# board_wifi_v2.net
KiCad netlist of a schematic drawn in EAGLE
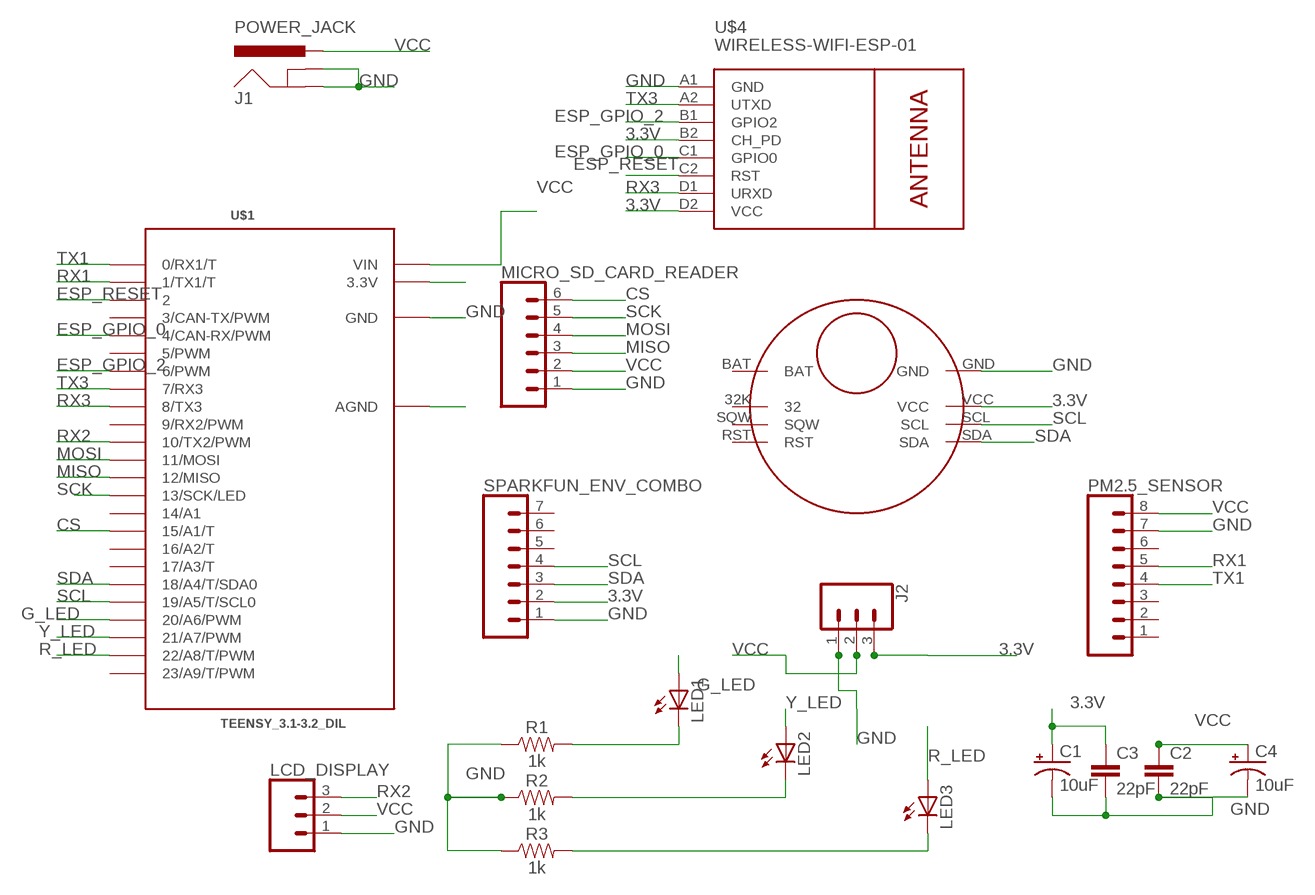
[diagram p0: schematic, sheet 1]

(export (version "E")
  (design (tool "Eeschema 10.0.6"))
  (components
    (comp (ref "C1")
      (value "10uF")
      (footprint "eagle-import:CPOL-RADIAL-2.5MM-5MM")
      (libsource (lib "eagle-import") (part "10UF-POLAR-RADIAL-2.5MM-25V-20%"))
    )
    (comp (ref "C2")
      (value "22pF")
      (footprint "eagle-import:CAP-PTH-2.54")
      (libsource (lib "eagle-import") (part "22PF-PTH-2.54MM-200V-5%"))
    )
    (comp (ref "C3")
      (value "22pF")
      (footprint "eagle-import:CAP-PTH-2.54")
      (libsource (lib "eagle-import") (part "22PF-PTH-2.54MM-200V-5%"))
    )
    (comp (ref "C4")
      (value "10uF")
      (footprint "eagle-import:CPOL-RADIAL-2.5MM-5MM")
      (libsource (lib "eagle-import") (part "10UF-POLAR-RADIAL-2.5MM-25V-20%"))
    )
    (comp (ref "J1")
      (value "POWER_JACK")
      (footprint "eagle-import:POWER_JACK_PTH")
      (libsource (lib "eagle-import") (part "POWER_JACK"))
    )
    (comp (ref "J2")
      (value "CONN_03LONGPADS")
      (footprint "eagle-import:1X03_LONGPADS")
      (libsource (lib "eagle-import") (part "CONN_03LONGPADS"))
    )
    (comp (ref "LCD_DISPLAY")
      (value "CONN_031X03_NO_SILK")
      (footprint "eagle-import:1X03_NO_SILK")
      (libsource (lib "eagle-import") (part "CONN_031X03_NO_SILK"))
    )
    (comp (ref "LED1")
      (value "LED3MM")
      (footprint "eagle-import:LED3MM")
      (libsource (lib "eagle-import") (part "LED3MM"))
    )
    (comp (ref "LED2")
      (value "LED3MM")
      (footprint "eagle-import:LED3MM")
      (libsource (lib "eagle-import") (part "LED3MM"))
    )
    (comp (ref "LED3")
      (value "LED3MM")
      (footprint "eagle-import:LED3MM")
      (libsource (lib "eagle-import") (part "LED3MM"))
    )
    (comp (ref "MICRO_SD_CARD_READER")
      (value "CONN_06LONGPADS")
      (footprint "eagle-import:1X06_LONGPADS")
      (libsource (lib "eagle-import") (part "CONN_06LONGPADS"))
    )
    (comp (ref "PM2.5_SENSOR")
      (value "CONN_08NO_SILK_FEMALE_PTH")
      (footprint "eagle-import:1X08_NO_SILK")
      (libsource (lib "eagle-import") (part "CONN_08NO_SILK_FEMALE_PTH"))
    )
    (comp (ref "R1")
      (value "1k")
      (footprint "eagle-import:AXIAL-0.3")
      (libsource (lib "eagle-import") (part "1KOHM-HORIZ-1/4W-5%"))
    )
    (comp (ref "R2")
      (value "1k")
      (footprint "eagle-import:AXIAL-0.3")
      (libsource (lib "eagle-import") (part "1KOHM-HORIZ-1/4W-5%"))
    )
    (comp (ref "R3")
      (value "1k")
      (footprint "eagle-import:AXIAL-0.3")
      (libsource (lib "eagle-import") (part "1KOHM-HORIZ-1/4W-5%"))
    )
    (comp (ref "SPARKFUN_ENV_COMBO")
      (value "CONN_07NO_SILK")
      (footprint "eagle-import:1X07_NO_SILK")
      (libsource (lib "eagle-import") (part "CONN_07NO_SILK"))
    )
    (comp (ref "U$1")
      (value "TEENSY_3.1-3.2_DIL")
      (footprint "eagle-import:TEENSY_3.0-3.2&LC_DIL")
      (libsource (lib "eagle-import") (part "TEENSY_3.1-3.2_DIL"))
    )
    (comp (ref "U$2")
      (value "RTCCLOCK")
      (footprint "eagle-import:RTCCLOCK")
      (libsource (lib "eagle-import") (part "RTCCLOCK"))
    )
    (comp (ref "U$4")
      (value "WIRELESS-WIFI-ESP-01")
      (footprint "eagle-import:WIRELESS-WIFI-ESP-01")
      (libsource (lib "eagle-import") (part "WIRELESS-WIFI-ESP-01"))
    )
  )
  (nets
    (net (code "1") (name "/3.3V") (class "Default")
      (node (ref "C1") (pin "1") (pinfunction "+_1") (pintype "passive"))
      (node (ref "C3") (pin "1") (pinfunction "1_1") (pintype "passive"))
      (node (ref "J2") (pin "3") (pinfunction "3_3") (pintype "passive"))
      (node (ref "SPARKFUN_ENV_COMBO") (pin "2") (pinfunction "2_2") (pintype "passive"))
      (node (ref "U$2") (pin "VCC") (pinfunction "VCC_VCC") (pintype "bidirectional"))
      (node (ref "U$4") (pin "B2") (pinfunction "CH_PD_B2") (pintype "bidirectional"))
      (node (ref "U$4") (pin "D2") (pinfunction "VCC_D2") (pintype "power_in"))
    )
    (net (code "2") (name "/CS") (class "Default")
      (node (ref "MICRO_SD_CARD_READER") (pin "6") (pinfunction "6_6") (pintype "passive"))
      (node (ref "U$1") (pin "15/A1") (pinfunction "15/A1/T_15/A1") (pintype "bidirectional"))
    )
    (net (code "3") (name "/ESP_GPIO_0") (class "Default")
      (node (ref "U$1") (pin "4") (pinfunction "4/CAN-RX/PWM_4") (pintype "bidirectional"))
      (node (ref "U$4") (pin "C1") (pinfunction "GPIO0_C1") (pintype "bidirectional"))
    )
    (net (code "4") (name "/ESP_GPIO_2") (class "Default")
      (node (ref "U$1") (pin "6") (pinfunction "6/PWM_6") (pintype "bidirectional"))
      (node (ref "U$4") (pin "B1") (pinfunction "GPIO2_B1") (pintype "bidirectional"))
    )
    (net (code "5") (name "/ESP_RESET") (class "Default")
      (node (ref "U$1") (pin "2") (pinfunction "2_2") (pintype "bidirectional"))
      (node (ref "U$4") (pin "C2") (pinfunction "RST_C2") (pintype "bidirectional"))
    )
    (net (code "6") (name "/GND") (class "Default")
      (node (ref "C1") (pin "2") (pinfunction "-_2") (pintype "passive"))
      (node (ref "C2") (pin "2") (pinfunction "2_2") (pintype "passive"))
      (node (ref "C3") (pin "2") (pinfunction "2_2") (pintype "passive"))
      (node (ref "C4") (pin "2") (pinfunction "-_2") (pintype "passive"))
      (node (ref "J1") (pin "GND") (pinfunction "GND_GND") (pintype "bidirectional"))
      (node (ref "J1") (pin "GNDBREAK") (pinfunction "GNDBREAK_GNDBREAK") (pintype "bidirectional"))
      (node (ref "J2") (pin "1") (pinfunction "1_1") (pintype "passive"))
      (node (ref "LCD_DISPLAY") (pin "1") (pinfunction "1_1") (pintype "passive"))
      (node (ref "MICRO_SD_CARD_READER") (pin "1") (pinfunction "1_1") (pintype "passive"))
      (node (ref "PM2.5_SENSOR") (pin "7") (pinfunction "7_7") (pintype "passive"))
      (node (ref "R1") (pin "P$1") (pinfunction "1_P$1") (pintype "passive"))
      (node (ref "R2") (pin "P$1") (pinfunction "1_P$1") (pintype "passive"))
      (node (ref "R3") (pin "P$1") (pinfunction "1_P$1") (pintype "passive"))
      (node (ref "SPARKFUN_ENV_COMBO") (pin "1") (pinfunction "1_1") (pintype "passive"))
      (node (ref "U$1") (pin "GND") (pinfunction "GND_GND") (pintype "power_in"))
      (node (ref "U$2") (pin "GND") (pinfunction "GND_GND") (pintype "bidirectional"))
      (node (ref "U$4") (pin "A1") (pinfunction "GND_A1") (pintype "power_in"))
    )
    (net (code "7") (name "/G_LED") (class "Default")
      (node (ref "LED1") (pin "A") (pinfunction "A_A") (pintype "passive"))
      (node (ref "U$1") (pin "20/A6") (pinfunction "20/A6/PWM_20/A6") (pintype "bidirectional"))
    )
    (net (code "8") (name "/MISO") (class "Default")
      (node (ref "MICRO_SD_CARD_READER") (pin "3") (pinfunction "3_3") (pintype "passive"))
      (node (ref "U$1") (pin "12") (pinfunction "12/MISO_12") (pintype "bidirectional"))
    )
    (net (code "9") (name "/MOSI") (class "Default")
      (node (ref "MICRO_SD_CARD_READER") (pin "4") (pinfunction "4_4") (pintype "passive"))
      (node (ref "U$1") (pin "11") (pinfunction "11/MOSI_11") (pintype "bidirectional"))
    )
    (net (code "10") (name "/RX1") (class "Default")
      (node (ref "PM2.5_SENSOR") (pin "5") (pinfunction "5_5") (pintype "passive"))
      (node (ref "U$1") (pin "1") (pinfunction "1/TX1/T_1") (pintype "bidirectional"))
    )
    (net (code "11") (name "/RX2") (class "Default")
      (node (ref "LCD_DISPLAY") (pin "3") (pinfunction "3_3") (pintype "passive"))
      (node (ref "U$1") (pin "10") (pinfunction "10/TX2/PWM_10") (pintype "bidirectional"))
    )
    (net (code "12") (name "/RX3") (class "Default")
      (node (ref "U$1") (pin "8") (pinfunction "8/TX3_8") (pintype "bidirectional"))
      (node (ref "U$4") (pin "D1") (pinfunction "URXD_D1") (pintype "bidirectional"))
    )
    (net (code "13") (name "/R_LED") (class "Default")
      (node (ref "LED3") (pin "A") (pinfunction "A_A") (pintype "passive"))
      (node (ref "U$1") (pin "22/A8") (pinfunction "22/A8/T/PWM_22/A8") (pintype "bidirectional"))
    )
    (net (code "14") (name "/SCK") (class "Default")
      (node (ref "MICRO_SD_CARD_READER") (pin "5") (pinfunction "5_5") (pintype "passive"))
      (node (ref "U$1") (pin "13") (pinfunction "13/SCK/LED_13") (pintype "bidirectional"))
    )
    (net (code "15") (name "/SCL") (class "Default")
      (node (ref "SPARKFUN_ENV_COMBO") (pin "4") (pinfunction "4_4") (pintype "passive"))
      (node (ref "U$1") (pin "19/A5") (pinfunction "19/A5/T/SCL0_19/A5") (pintype "bidirectional"))
      (node (ref "U$2") (pin "SCL") (pinfunction "SCL_SCL") (pintype "bidirectional"))
    )
    (net (code "16") (name "/SDA") (class "Default")
      (node (ref "SPARKFUN_ENV_COMBO") (pin "3") (pinfunction "3_3") (pintype "passive"))
      (node (ref "U$1") (pin "18/A4") (pinfunction "18/A4/T/SDA0_18/A4") (pintype "bidirectional"))
      (node (ref "U$2") (pin "SDA") (pinfunction "SDA_SDA") (pintype "bidirectional"))
    )
    (net (code "17") (name "/TX1") (class "Default")
      (node (ref "PM2.5_SENSOR") (pin "4") (pinfunction "4_4") (pintype "passive"))
      (node (ref "U$1") (pin "0") (pinfunction "0/RX1/T_0") (pintype "bidirectional"))
    )
    (net (code "18") (name "/TX3") (class "Default")
      (node (ref "U$1") (pin "7") (pinfunction "7/RX3_7") (pintype "bidirectional"))
      (node (ref "U$4") (pin "A2") (pinfunction "UTXD_A2") (pintype "bidirectional"))
    )
    (net (code "19") (name "/VCC") (class "Default")
      (node (ref "C2") (pin "1") (pinfunction "1_1") (pintype "passive"))
      (node (ref "C4") (pin "1") (pinfunction "+_1") (pintype "passive"))
      (node (ref "J1") (pin "PWR") (pinfunction "PWR_PWR") (pintype "bidirectional"))
      (node (ref "J2") (pin "2") (pinfunction "2_2") (pintype "passive"))
      (node (ref "LCD_DISPLAY") (pin "2") (pinfunction "2_2") (pintype "passive"))
      (node (ref "MICRO_SD_CARD_READER") (pin "2") (pinfunction "2_2") (pintype "passive"))
      (node (ref "PM2.5_SENSOR") (pin "8") (pinfunction "8_8") (pintype "passive"))
      (node (ref "U$1") (pin "VIN") (pinfunction "VIN_VIN") (pintype "power_in"))
    )
    (net (code "20") (name "/Y_LED") (class "Default")
      (node (ref "LED2") (pin "A") (pinfunction "A_A") (pintype "passive"))
      (node (ref "U$1") (pin "21/A7") (pinfunction "21/A7/PWM_21/A7") (pintype "bidirectional"))
    )
    (net (code "21") (name "Net-(LED1-C)") (class "Default")
      (node (ref "LED1") (pin "K") (pinfunction "C_K") (pintype "passive"))
      (node (ref "R1") (pin "P$2") (pinfunction "2_P$2") (pintype "passive"))
    )
    (net (code "22") (name "Net-(LED2-C)") (class "Default")
      (node (ref "LED2") (pin "K") (pinfunction "C_K") (pintype "passive"))
      (node (ref "R2") (pin "P$2") (pinfunction "2_P$2") (pintype "passive"))
    )
    (net (code "23") (name "Net-(LED3-C)") (class "Default")
      (node (ref "LED3") (pin "K") (pinfunction "C_K") (pintype "passive"))
      (node (ref "R3") (pin "P$2") (pinfunction "2_P$2") (pintype "passive"))
    )
    (net (code "24") (name "unconnected-(PM2.5_SENSOR-Pad1)") (class "Default")
      (node (ref "PM2.5_SENSOR") (pin "1") (pinfunction "1_1") (pintype "passive"))
    )
    (net (code "25") (name "unconnected-(PM2.5_SENSOR-Pad2)") (class "Default")
      (node (ref "PM2.5_SENSOR") (pin "2") (pinfunction "2_2") (pintype "passive"))
    )
    (net (code "26") (name "unconnected-(PM2.5_SENSOR-Pad3)") (class "Default")
      (node (ref "PM2.5_SENSOR") (pin "3") (pinfunction "3_3") (pintype "passive"))
    )
    (net (code "27") (name "unconnected-(PM2.5_SENSOR-Pad6)") (class "Default")
      (node (ref "PM2.5_SENSOR") (pin "6") (pinfunction "6_6") (pintype "passive"))
    )
    (net (code "28") (name "unconnected-(SPARKFUN_ENV_COMBO-Pad5)") (class "Default")
      (node (ref "SPARKFUN_ENV_COMBO") (pin "5") (pinfunction "5_5") (pintype "passive"))
    )
    (net (code "29") (name "unconnected-(SPARKFUN_ENV_COMBO-Pad6)") (class "Default")
      (node (ref "SPARKFUN_ENV_COMBO") (pin "6") (pinfunction "6_6") (pintype "passive"))
    )
    (net (code "30") (name "unconnected-(SPARKFUN_ENV_COMBO-Pad7)") (class "Default")
      (node (ref "SPARKFUN_ENV_COMBO") (pin "7") (pinfunction "7_7") (pintype "passive"))
    )
    (net (code "31") (name "unconnected-(U$1-3{slash}CAN-TX{slash}PWM-Pad3)") (class "Default")
      (node (ref "U$1") (pin "3") (pinfunction "3/CAN-TX/PWM_3") (pintype "bidirectional"))
    )
    (net (code "32") (name "unconnected-(U$1-5{slash}PWM-Pad5)") (class "Default")
      (node (ref "U$1") (pin "5") (pinfunction "5/PWM_5") (pintype "bidirectional"))
    )
    (net (code "33") (name "unconnected-(U$1-9{slash}RX2{slash}PWM-Pad9)") (class "Default")
      (node (ref "U$1") (pin "9") (pinfunction "9/RX2/PWM_9") (pintype "bidirectional"))
    )
    (net (code "34") (name "unconnected-(U$1-14{slash}A1-Pad14{slash}A0)") (class "Default")
      (node (ref "U$1") (pin "14/A0") (pinfunction "14/A1_14/A0") (pintype "bidirectional"))
    )
    (net (code "35") (name "unconnected-(U$1-16{slash}A2{slash}T-Pad16{slash}A2)") (class "Default")
      (node (ref "U$1") (pin "16/A2") (pinfunction "16/A2/T_16/A2") (pintype "bidirectional"))
    )
    (net (code "36") (name "unconnected-(U$1-17{slash}A3{slash}T-Pad17{slash}A3)") (class "Default")
      (node (ref "U$1") (pin "17/A3") (pinfunction "17/A3/T_17/A3") (pintype "bidirectional"))
    )
    (net (code "37") (name "unconnected-(U$1-23{slash}A9{slash}T{slash}PWM-Pad23{slash}A9)") (class "Default")
      (node (ref "U$1") (pin "23/A9") (pinfunction "23/A9/T/PWM_23/A9") (pintype "bidirectional"))
    )
    (net (code "38") (name "unconnected-(U$1-Pad3.3V)") (class "Default")
      (node (ref "U$1") (pin "3.3V") (pinfunction "3.3V_3.3V") (pintype "power_in"))
    )
    (net (code "39") (name "unconnected-(U$1-PadAGND)") (class "Default")
      (node (ref "U$1") (pin "AGND") (pinfunction "AGND_AGND") (pintype "power_in"))
    )
    (net (code "40") (name "unconnected-(U$2-32-Pad32K)") (class "Default")
      (node (ref "U$2") (pin "32K") (pinfunction "32_32K") (pintype "bidirectional"))
    )
    (net (code "41") (name "unconnected-(U$2-PadBAT)") (class "Default")
      (node (ref "U$2") (pin "BAT") (pinfunction "BAT_BAT") (pintype "bidirectional"))
    )
    (net (code "42") (name "unconnected-(U$2-PadRST)") (class "Default")
      (node (ref "U$2") (pin "RST") (pinfunction "RST_RST") (pintype "bidirectional"))
    )
    (net (code "43") (name "unconnected-(U$2-PadSQW)") (class "Default")
      (node (ref "U$2") (pin "SQW") (pinfunction "SQW_SQW") (pintype "bidirectional"))
    )
  )
)
